# power.net
KiCad netlist of a schematic drawn in Altium Designer
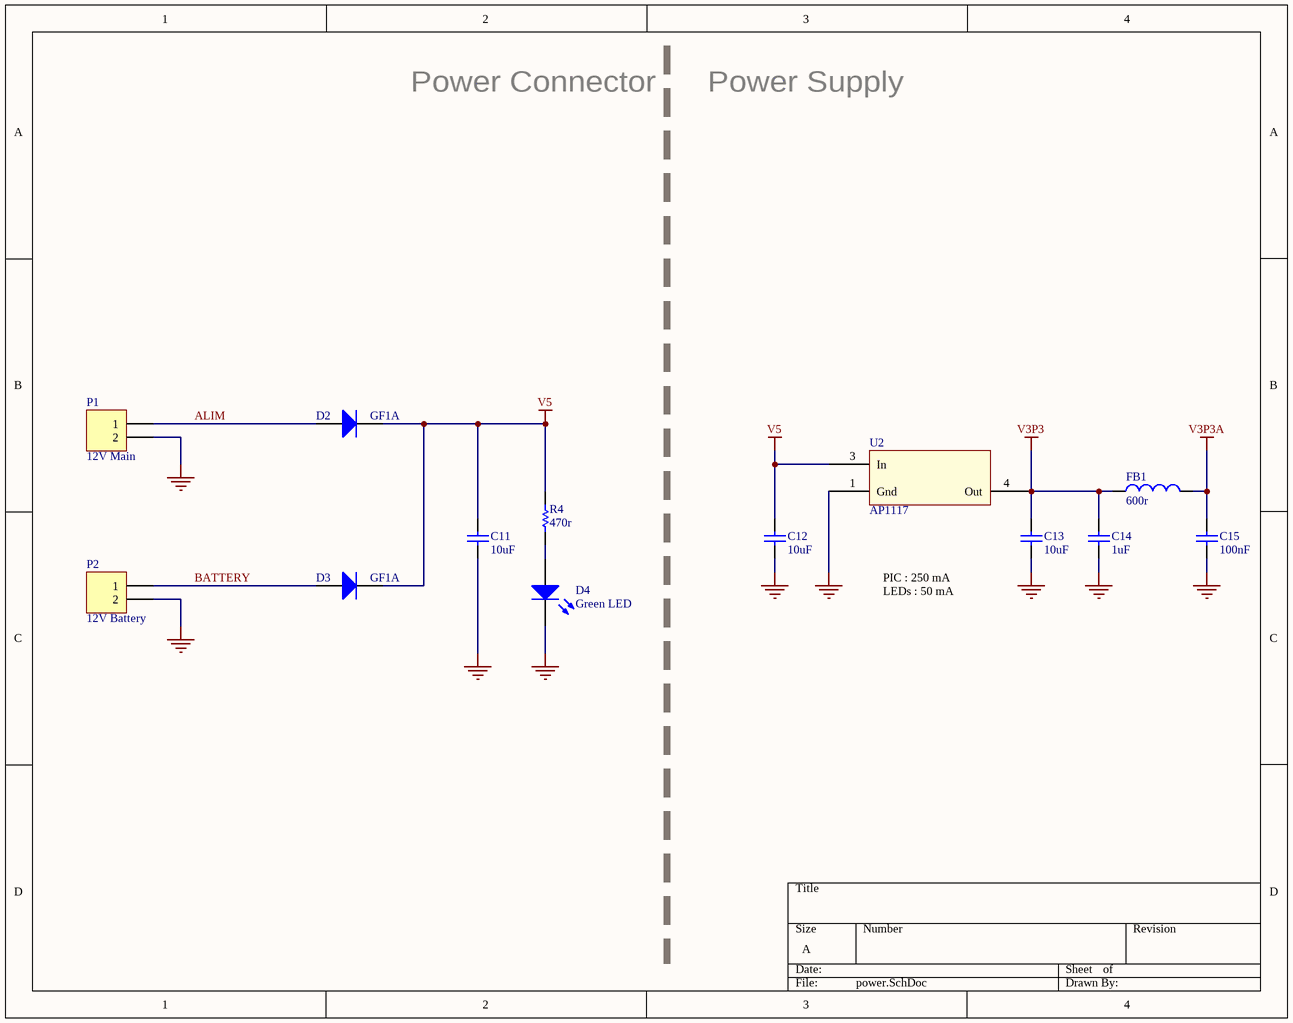
[diagram p0: power.SchDoc]

(export (version "E")
  (design (tool "Eeschema 10.0.6"))
  (components
    (comp (ref "C11")
      (value "10uF")
      (footprint "CAPC2012N")
      (description "Capacitor")
      (fields (field (name "PUBLISHER") "Altium Limited"))
      (libsource (lib "Miscellaneous Devices") (part "Cap"))
    )
    (comp (ref "C12")
      (value "10uF")
      (footprint "CAPC2012N")
      (description "Capacitor")
      (fields (field (name "PUBLISHER") "Altium Limited"))
      (libsource (lib "Miscellaneous Devices") (part "Cap"))
    )
    (comp (ref "C13")
      (value "10uF")
      (footprint "CAPC2012N")
      (description "Capacitor")
      (fields (field (name "PUBLISHER") "Altium Limited"))
      (libsource (lib "Miscellaneous Devices") (part "Cap"))
    )
    (comp (ref "C14")
      (value "1uF")
      (footprint "CAPC1608N")
      (description "Capacitor")
      (fields (field (name "PUBLISHER") "Altium Limited"))
      (libsource (lib "Miscellaneous Devices") (part "Cap"))
    )
    (comp (ref "C15")
      (value "100nF")
      (footprint "CAPC1608N")
      (description "Capacitor")
      (fields (field (name "PUBLISHER") "Altium Limited"))
      (libsource (lib "Miscellaneous Devices") (part "Cap"))
    )
    (comp (ref "D2")
      (value "GF1A")
      (footprint "SMA/DO-214AC_21")
      (description "Default Diode")
      (fields (field (name "PUBLISHER") "Altium Limited"))
      (libsource (lib "Miscellaneous Devices") (part "Diode"))
    )
    (comp (ref "D3")
      (value "GF1A")
      (footprint "SMA/DO-214AC_21")
      (description "Default Diode")
      (fields (field (name "PUBLISHER") "Altium Limited"))
      (libsource (lib "Miscellaneous Devices") (part "Diode"))
    )
    (comp (ref "D4")
      (value "Green LED")
      (footprint "LED 0805")
      (description "Typical INFRARED GaAs LED")
      (fields (field (name "PUBLISHER") "Altium Limited"))
      (libsource (lib "Miscellaneous Devices") (part "LED0"))
    )
    (comp (ref "FB1")
      (value "600r")
      (footprint "INDC1608AN")
      (description "Inductor")
      (fields (field (name "PUBLISHER") "Altium Limited"))
      (libsource (lib "Miscellaneous Devices") (part "Inductor"))
    )
    (comp (ref "P1")
      (value "12V Main")
      (footprint "PHOENIX_1985195")
      (description "Header, 2-Pin")
      (fields (field (name "PUBLISHER") "Altium Limited"))
      (libsource (lib "Miscellaneous Connectors") (part "Header 2"))
    )
    (comp (ref "P2")
      (value "12V Battery")
      (footprint "PHOENIX_1985195")
      (description "Header, 2-Pin")
      (fields (field (name "PUBLISHER") "Altium Limited"))
      (libsource (lib "Miscellaneous Connectors") (part "Header 2"))
    )
    (comp (ref "R4")
      (value "470r")
      (footprint "RESC1608N")
      (description "Resistor")
      (fields (field (name "PUBLISHER") "Altium Limited"))
      (libsource (lib "Miscellaneous Devices") (part "Res1"))
    )
    (comp (ref "U2")
      (value "AP1117")
      (footprint "TD03B_N")
      (description "1A LDO, 18V input, DPAK")
      (libsource (lib "TP2") (part "AP1117"))
    )
  )
  (nets
    (net (code "1") (name "/ALIM") (class "Default")
      (node (ref "D2") (pin "1") (pinfunction "A_1") (pintype "passive"))
      (node (ref "P1") (pin "1") (pinfunction "1_1") (pintype "passive"))
    )
    (net (code "2") (name "/BATTERY") (class "Default")
      (node (ref "D3") (pin "1") (pinfunction "A_1") (pintype "passive"))
      (node (ref "P2") (pin "1") (pinfunction "1_1") (pintype "passive"))
    )
    (net (code "3") (name "GND") (class "Default")
      (node (ref "C11") (pin "1") (pinfunction "1_1") (pintype "passive"))
      (node (ref "C12") (pin "2") (pinfunction "2_2") (pintype "passive"))
      (node (ref "C13") (pin "2") (pinfunction "2_2") (pintype "passive"))
      (node (ref "C14") (pin "1") (pinfunction "1_1") (pintype "passive"))
      (node (ref "C15") (pin "1") (pinfunction "1_1") (pintype "passive"))
      (node (ref "D4") (pin "2") (pinfunction "K_2") (pintype "passive"))
      (node (ref "P1") (pin "2") (pinfunction "2_2") (pintype "passive"))
      (node (ref "P2") (pin "2") (pinfunction "2_2") (pintype "passive"))
      (node (ref "U2") (pin "1") (pinfunction "Gnd_1") (pintype "power_in"))
    )
    (net (code "4") (name "Net-(D4-A)") (class "Default")
      (node (ref "D4") (pin "1") (pinfunction "A_1") (pintype "passive"))
      (node (ref "R4") (pin "1") (pinfunction "1_1") (pintype "passive"))
    )
    (net (code "5") (name "V3P3") (class "Default")
      (node (ref "C13") (pin "1") (pinfunction "1_1") (pintype "passive"))
      (node (ref "C14") (pin "2") (pinfunction "2_2") (pintype "passive"))
      (node (ref "FB1") (pin "1") (pinfunction "1_1") (pintype "passive"))
      (node (ref "U2") (pin "4") (pinfunction "Out_4") (pintype "power_in"))
    )
    (net (code "6") (name "V3P3A") (class "Default")
      (node (ref "C15") (pin "2") (pinfunction "2_2") (pintype "passive"))
      (node (ref "FB1") (pin "2") (pinfunction "2_2") (pintype "passive"))
    )
    (net (code "7") (name "V5") (class "Default")
      (node (ref "C11") (pin "2") (pinfunction "2_2") (pintype "passive"))
      (node (ref "C12") (pin "1") (pinfunction "1_1") (pintype "passive"))
      (node (ref "D2") (pin "2") (pinfunction "K_2") (pintype "passive"))
      (node (ref "D3") (pin "2") (pinfunction "K_2") (pintype "passive"))
      (node (ref "R4") (pin "2") (pinfunction "2_2") (pintype "passive"))
      (node (ref "U2") (pin "3") (pinfunction "In_3") (pintype "power_in"))
    )
  )
)
